# Boost_Bar.net
KiCad netlist of a schematic drawn in Altium Designer
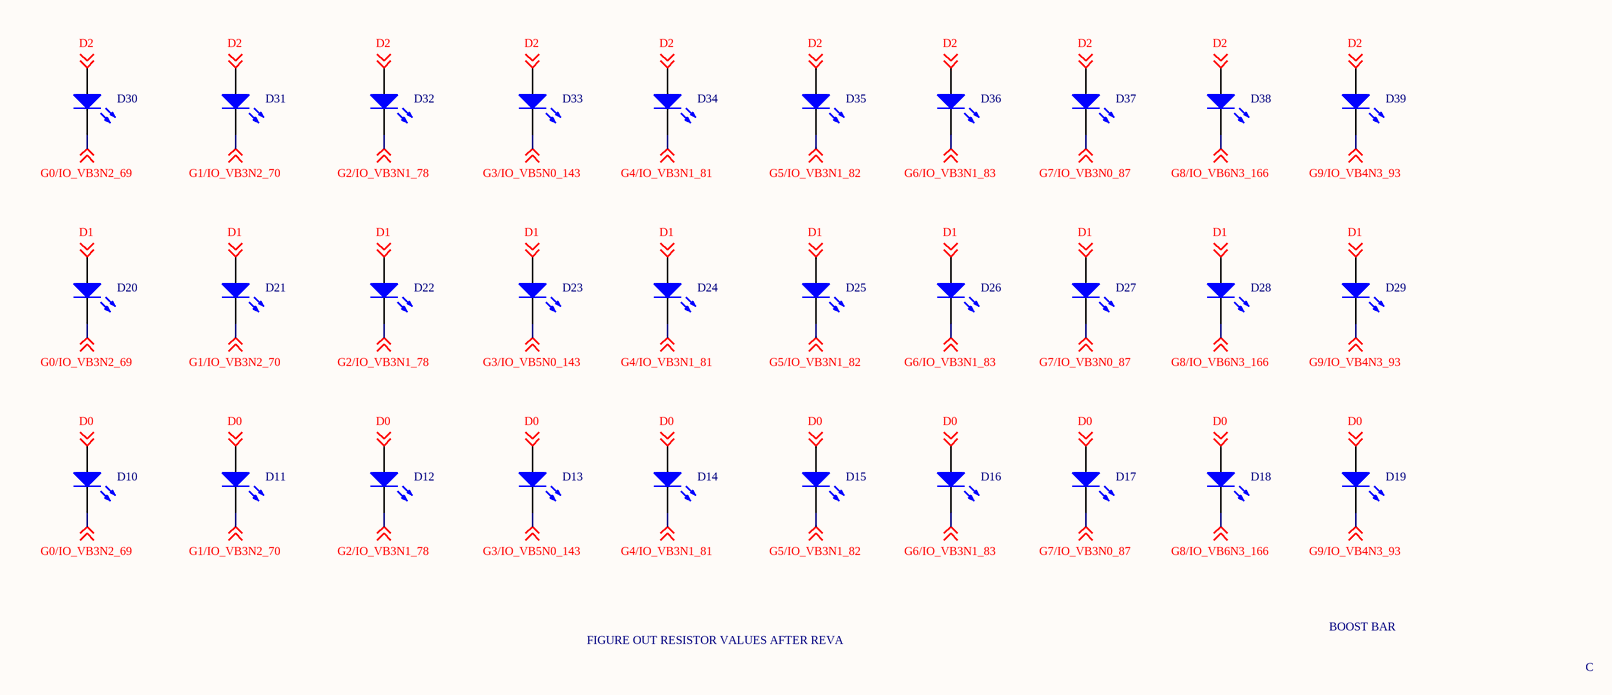
[diagram p0: Boost_Bar.SchDoc]

(export (version "E")
  (design (tool "Eeschema 10.0.6"))
  (components
    (comp (ref "D10")
      (value "~")
      (footprint "DIODE_0603")
      (description "Typical INFRARED GaAs LED")
      (fields (field (name "PUBLISHER") "Altium Limited"))
      (libsource (lib "Miscellaneous Devices") (part "LED0"))
    )
    (comp (ref "D11")
      (value "~")
      (footprint "DIODE_0603")
      (description "Typical INFRARED GaAs LED")
      (fields (field (name "PUBLISHER") "Altium Limited"))
      (libsource (lib "Miscellaneous Devices") (part "LED0"))
    )
    (comp (ref "D12")
      (value "~")
      (footprint "DIODE_0603")
      (description "Typical INFRARED GaAs LED")
      (fields (field (name "PUBLISHER") "Altium Limited"))
      (libsource (lib "Miscellaneous Devices") (part "LED0"))
    )
    (comp (ref "D13")
      (value "~")
      (footprint "DIODE_0603")
      (description "Typical INFRARED GaAs LED")
      (fields (field (name "PUBLISHER") "Altium Limited"))
      (libsource (lib "Miscellaneous Devices") (part "LED0"))
    )
    (comp (ref "D14")
      (value "~")
      (footprint "DIODE_0603")
      (description "Typical INFRARED GaAs LED")
      (fields (field (name "PUBLISHER") "Altium Limited"))
      (libsource (lib "Miscellaneous Devices") (part "LED0"))
    )
    (comp (ref "D15")
      (value "~")
      (footprint "DIODE_0603")
      (description "Typical INFRARED GaAs LED")
      (fields (field (name "PUBLISHER") "Altium Limited"))
      (libsource (lib "Miscellaneous Devices") (part "LED0"))
    )
    (comp (ref "D16")
      (value "~")
      (footprint "DIODE_0603")
      (description "Typical INFRARED GaAs LED")
      (fields (field (name "PUBLISHER") "Altium Limited"))
      (libsource (lib "Miscellaneous Devices") (part "LED0"))
    )
    (comp (ref "D17")
      (value "~")
      (footprint "DIODE_0603")
      (description "Typical INFRARED GaAs LED")
      (fields (field (name "PUBLISHER") "Altium Limited"))
      (libsource (lib "Miscellaneous Devices") (part "LED0"))
    )
    (comp (ref "D18")
      (value "~")
      (footprint "DIODE_0603")
      (description "Typical INFRARED GaAs LED")
      (fields (field (name "PUBLISHER") "Altium Limited"))
      (libsource (lib "Miscellaneous Devices") (part "LED0"))
    )
    (comp (ref "D19")
      (value "~")
      (footprint "DIODE_0603")
      (description "Typical INFRARED GaAs LED")
      (fields (field (name "PUBLISHER") "Altium Limited"))
      (libsource (lib "Miscellaneous Devices") (part "LED0"))
    )
    (comp (ref "D20")
      (value "~")
      (footprint "DIODE_0603")
      (description "Typical INFRARED GaAs LED")
      (fields (field (name "PUBLISHER") "Altium Limited"))
      (libsource (lib "Miscellaneous Devices") (part "LED0"))
    )
    (comp (ref "D21")
      (value "~")
      (footprint "DIODE_0603")
      (description "Typical INFRARED GaAs LED")
      (fields (field (name "PUBLISHER") "Altium Limited"))
      (libsource (lib "Miscellaneous Devices") (part "LED0"))
    )
    (comp (ref "D22")
      (value "~")
      (footprint "DIODE_0603")
      (description "Typical INFRARED GaAs LED")
      (fields (field (name "PUBLISHER") "Altium Limited"))
      (libsource (lib "Miscellaneous Devices") (part "LED0"))
    )
    (comp (ref "D23")
      (value "~")
      (footprint "DIODE_0603")
      (description "Typical INFRARED GaAs LED")
      (fields (field (name "PUBLISHER") "Altium Limited"))
      (libsource (lib "Miscellaneous Devices") (part "LED0"))
    )
    (comp (ref "D24")
      (value "~")
      (footprint "DIODE_0603")
      (description "Typical INFRARED GaAs LED")
      (fields (field (name "PUBLISHER") "Altium Limited"))
      (libsource (lib "Miscellaneous Devices") (part "LED0"))
    )
    (comp (ref "D25")
      (value "~")
      (footprint "DIODE_0603")
      (description "Typical INFRARED GaAs LED")
      (fields (field (name "PUBLISHER") "Altium Limited"))
      (libsource (lib "Miscellaneous Devices") (part "LED0"))
    )
    (comp (ref "D26")
      (value "~")
      (footprint "DIODE_0603")
      (description "Typical INFRARED GaAs LED")
      (fields (field (name "PUBLISHER") "Altium Limited"))
      (libsource (lib "Miscellaneous Devices") (part "LED0"))
    )
    (comp (ref "D27")
      (value "~")
      (footprint "DIODE_0603")
      (description "Typical INFRARED GaAs LED")
      (fields (field (name "PUBLISHER") "Altium Limited"))
      (libsource (lib "Miscellaneous Devices") (part "LED0"))
    )
    (comp (ref "D28")
      (value "~")
      (footprint "DIODE_0603")
      (description "Typical INFRARED GaAs LED")
      (fields (field (name "PUBLISHER") "Altium Limited"))
      (libsource (lib "Miscellaneous Devices") (part "LED0"))
    )
    (comp (ref "D29")
      (value "~")
      (footprint "DIODE_0603")
      (description "Typical INFRARED GaAs LED")
      (fields (field (name "PUBLISHER") "Altium Limited"))
      (libsource (lib "Miscellaneous Devices") (part "LED0"))
    )
    (comp (ref "D30")
      (value "~")
      (footprint "DIODE_0603")
      (description "Typical INFRARED GaAs LED")
      (fields (field (name "PUBLISHER") "Altium Limited"))
      (libsource (lib "Miscellaneous Devices") (part "LED0"))
    )
    (comp (ref "D31")
      (value "~")
      (footprint "DIODE_0603")
      (description "Typical INFRARED GaAs LED")
      (fields (field (name "PUBLISHER") "Altium Limited"))
      (libsource (lib "Miscellaneous Devices") (part "LED0"))
    )
    (comp (ref "D32")
      (value "~")
      (footprint "DIODE_0603")
      (description "Typical INFRARED GaAs LED")
      (fields (field (name "PUBLISHER") "Altium Limited"))
      (libsource (lib "Miscellaneous Devices") (part "LED0"))
    )
    (comp (ref "D33")
      (value "~")
      (footprint "DIODE_0603")
      (description "Typical INFRARED GaAs LED")
      (fields (field (name "PUBLISHER") "Altium Limited"))
      (libsource (lib "Miscellaneous Devices") (part "LED0"))
    )
    (comp (ref "D34")
      (value "~")
      (footprint "DIODE_0603")
      (description "Typical INFRARED GaAs LED")
      (fields (field (name "PUBLISHER") "Altium Limited"))
      (libsource (lib "Miscellaneous Devices") (part "LED0"))
    )
    (comp (ref "D35")
      (value "~")
      (footprint "DIODE_0603")
      (description "Typical INFRARED GaAs LED")
      (fields (field (name "PUBLISHER") "Altium Limited"))
      (libsource (lib "Miscellaneous Devices") (part "LED0"))
    )
    (comp (ref "D36")
      (value "~")
      (footprint "DIODE_0603")
      (description "Typical INFRARED GaAs LED")
      (fields (field (name "PUBLISHER") "Altium Limited"))
      (libsource (lib "Miscellaneous Devices") (part "LED0"))
    )
    (comp (ref "D37")
      (value "~")
      (footprint "DIODE_0603")
      (description "Typical INFRARED GaAs LED")
      (fields (field (name "PUBLISHER") "Altium Limited"))
      (libsource (lib "Miscellaneous Devices") (part "LED0"))
    )
    (comp (ref "D38")
      (value "~")
      (footprint "DIODE_0603")
      (description "Typical INFRARED GaAs LED")
      (fields (field (name "PUBLISHER") "Altium Limited"))
      (libsource (lib "Miscellaneous Devices") (part "LED0"))
    )
    (comp (ref "D39")
      (value "~")
      (footprint "DIODE_0603")
      (description "Typical INFRARED GaAs LED")
      (fields (field (name "PUBLISHER") "Altium Limited"))
      (libsource (lib "Miscellaneous Devices") (part "LED0"))
    )
  )
  (nets
    (net (code "1") (name "D0") (class "Default")
      (node (ref "D10") (pin "1") (pinfunction "A_1") (pintype "passive"))
      (node (ref "D11") (pin "1") (pinfunction "A_1") (pintype "passive"))
      (node (ref "D12") (pin "1") (pinfunction "A_1") (pintype "passive"))
      (node (ref "D13") (pin "1") (pinfunction "A_1") (pintype "passive"))
      (node (ref "D14") (pin "1") (pinfunction "A_1") (pintype "passive"))
      (node (ref "D15") (pin "1") (pinfunction "A_1") (pintype "passive"))
      (node (ref "D16") (pin "1") (pinfunction "A_1") (pintype "passive"))
      (node (ref "D17") (pin "1") (pinfunction "A_1") (pintype "passive"))
      (node (ref "D18") (pin "1") (pinfunction "A_1") (pintype "passive"))
      (node (ref "D19") (pin "1") (pinfunction "A_1") (pintype "passive"))
    )
    (net (code "2") (name "D1") (class "Default")
      (node (ref "D20") (pin "1") (pinfunction "A_1") (pintype "passive"))
      (node (ref "D21") (pin "1") (pinfunction "A_1") (pintype "passive"))
      (node (ref "D22") (pin "1") (pinfunction "A_1") (pintype "passive"))
      (node (ref "D23") (pin "1") (pinfunction "A_1") (pintype "passive"))
      (node (ref "D24") (pin "1") (pinfunction "A_1") (pintype "passive"))
      (node (ref "D25") (pin "1") (pinfunction "A_1") (pintype "passive"))
      (node (ref "D26") (pin "1") (pinfunction "A_1") (pintype "passive"))
      (node (ref "D27") (pin "1") (pinfunction "A_1") (pintype "passive"))
      (node (ref "D28") (pin "1") (pinfunction "A_1") (pintype "passive"))
      (node (ref "D29") (pin "1") (pinfunction "A_1") (pintype "passive"))
    )
    (net (code "3") (name "D2") (class "Default")
      (node (ref "D30") (pin "1") (pinfunction "A_1") (pintype "passive"))
      (node (ref "D31") (pin "1") (pinfunction "A_1") (pintype "passive"))
      (node (ref "D32") (pin "1") (pinfunction "A_1") (pintype "passive"))
      (node (ref "D33") (pin "1") (pinfunction "A_1") (pintype "passive"))
      (node (ref "D34") (pin "1") (pinfunction "A_1") (pintype "passive"))
      (node (ref "D35") (pin "1") (pinfunction "A_1") (pintype "passive"))
      (node (ref "D36") (pin "1") (pinfunction "A_1") (pintype "passive"))
      (node (ref "D37") (pin "1") (pinfunction "A_1") (pintype "passive"))
      (node (ref "D38") (pin "1") (pinfunction "A_1") (pintype "passive"))
      (node (ref "D39") (pin "1") (pinfunction "A_1") (pintype "passive"))
    )
    (net (code "4") (name "G0{slash}IO_VB3N2_69") (class "Default")
      (node (ref "D10") (pin "2") (pinfunction "K_2") (pintype "passive"))
      (node (ref "D20") (pin "2") (pinfunction "K_2") (pintype "passive"))
      (node (ref "D30") (pin "2") (pinfunction "K_2") (pintype "passive"))
    )
    (net (code "5") (name "G1{slash}IO_VB3N2_70") (class "Default")
      (node (ref "D11") (pin "2") (pinfunction "K_2") (pintype "passive"))
      (node (ref "D21") (pin "2") (pinfunction "K_2") (pintype "passive"))
      (node (ref "D31") (pin "2") (pinfunction "K_2") (pintype "passive"))
    )
    (net (code "6") (name "G2{slash}IO_VB3N1_78") (class "Default")
      (node (ref "D12") (pin "2") (pinfunction "K_2") (pintype "passive"))
      (node (ref "D22") (pin "2") (pinfunction "K_2") (pintype "passive"))
      (node (ref "D32") (pin "2") (pinfunction "K_2") (pintype "passive"))
    )
    (net (code "7") (name "G3{slash}IO_VB5N0_143") (class "Default")
      (node (ref "D13") (pin "2") (pinfunction "K_2") (pintype "passive"))
      (node (ref "D23") (pin "2") (pinfunction "K_2") (pintype "passive"))
      (node (ref "D33") (pin "2") (pinfunction "K_2") (pintype "passive"))
    )
    (net (code "8") (name "G4{slash}IO_VB3N1_81") (class "Default")
      (node (ref "D14") (pin "2") (pinfunction "K_2") (pintype "passive"))
      (node (ref "D24") (pin "2") (pinfunction "K_2") (pintype "passive"))
      (node (ref "D34") (pin "2") (pinfunction "K_2") (pintype "passive"))
    )
    (net (code "9") (name "G5{slash}IO_VB3N1_82") (class "Default")
      (node (ref "D15") (pin "2") (pinfunction "K_2") (pintype "passive"))
      (node (ref "D25") (pin "2") (pinfunction "K_2") (pintype "passive"))
      (node (ref "D35") (pin "2") (pinfunction "K_2") (pintype "passive"))
    )
    (net (code "10") (name "G6{slash}IO_VB3N1_83") (class "Default")
      (node (ref "D16") (pin "2") (pinfunction "K_2") (pintype "passive"))
      (node (ref "D26") (pin "2") (pinfunction "K_2") (pintype "passive"))
      (node (ref "D36") (pin "2") (pinfunction "K_2") (pintype "passive"))
    )
    (net (code "11") (name "G7{slash}IO_VB3N0_87") (class "Default")
      (node (ref "D17") (pin "2") (pinfunction "K_2") (pintype "passive"))
      (node (ref "D27") (pin "2") (pinfunction "K_2") (pintype "passive"))
      (node (ref "D37") (pin "2") (pinfunction "K_2") (pintype "passive"))
    )
    (net (code "12") (name "G8{slash}IO_VB6N3_166") (class "Default")
      (node (ref "D18") (pin "2") (pinfunction "K_2") (pintype "passive"))
      (node (ref "D28") (pin "2") (pinfunction "K_2") (pintype "passive"))
      (node (ref "D38") (pin "2") (pinfunction "K_2") (pintype "passive"))
    )
    (net (code "13") (name "G9{slash}IO_VB4N3_93") (class "Default")
      (node (ref "D19") (pin "2") (pinfunction "K_2") (pintype "passive"))
      (node (ref "D29") (pin "2") (pinfunction "K_2") (pintype "passive"))
      (node (ref "D39") (pin "2") (pinfunction "K_2") (pintype "passive"))
    )
  )
)
